# circuit.net
KiCad netlist of a schematic drawn in Altium Designer
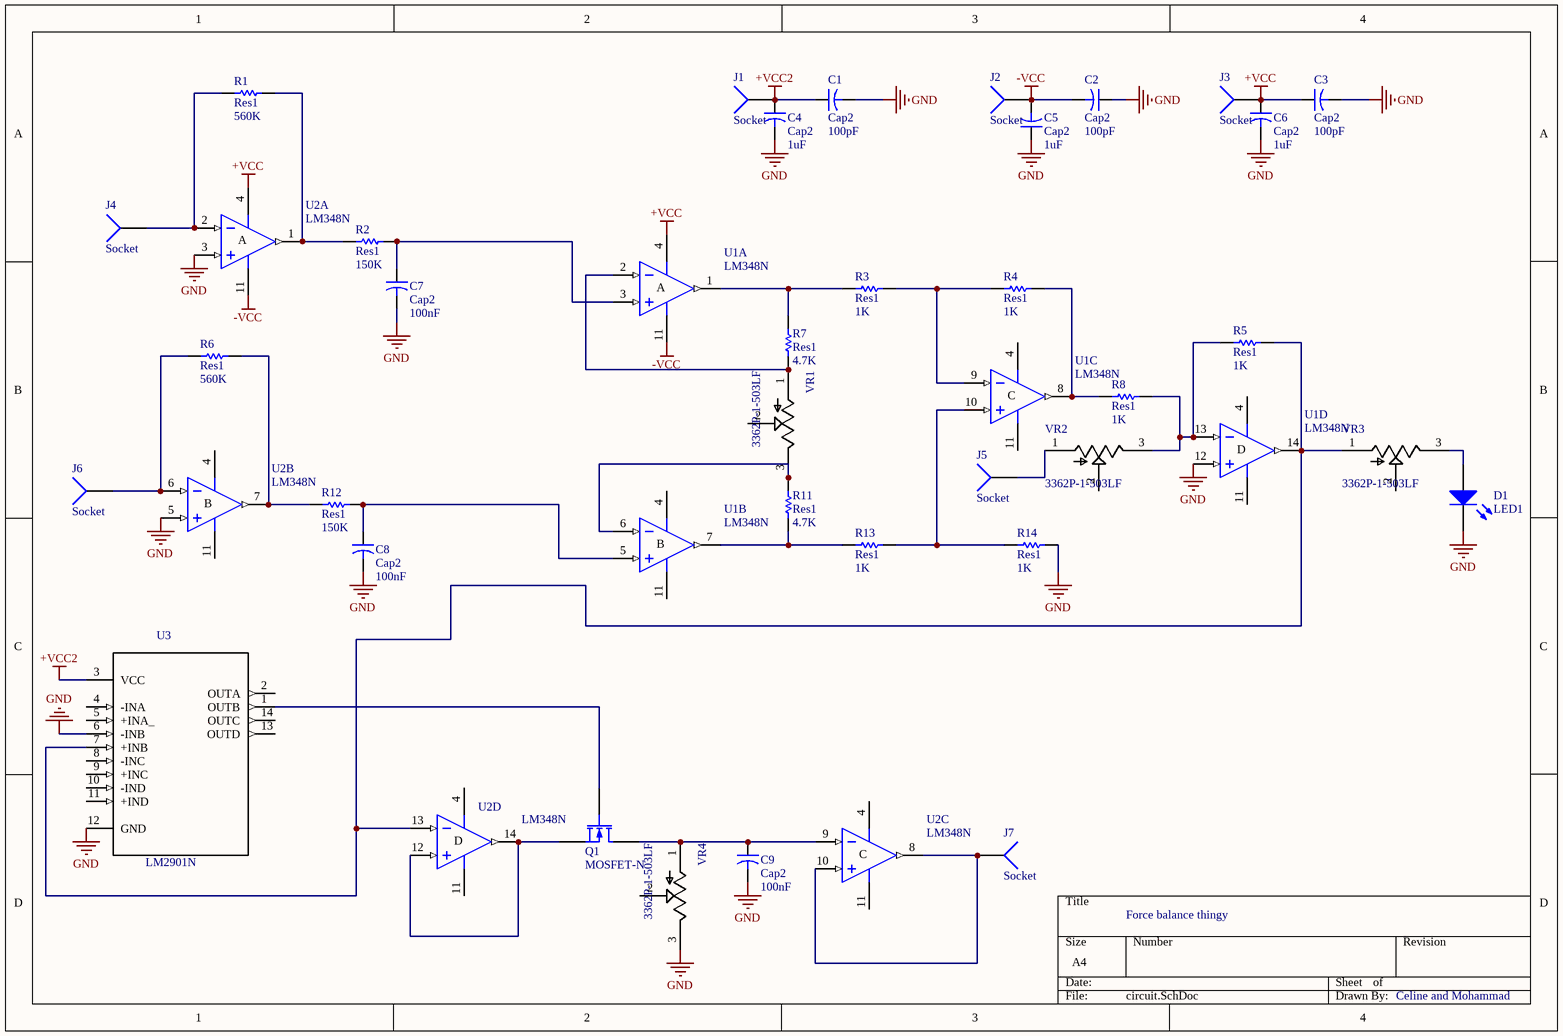
[diagram p0: circuit.SchDoc]

(export (version "E")
  (design (tool "Eeschema 10.0.6"))
  (components
    (comp (ref "C1")
      (value "Cap2")
      (footprint "CAPR5-4X5")
      (description "Capacitor")
      (fields (field (name "ALTIUM_VALUE") "100pF") (field (name "PUBLISHER") "Altium Limited"))
      (libsource (lib "Miscellaneous Devices") (part "Cap2"))
    )
    (comp (ref "C2")
      (value "Cap2")
      (footprint "CAPR5-4X5")
      (description "Capacitor")
      (fields (field (name "ALTIUM_VALUE") "100pF") (field (name "PUBLISHER") "Altium Limited"))
      (libsource (lib "Miscellaneous Devices") (part "Cap2"))
    )
    (comp (ref "C3")
      (value "Cap2")
      (footprint "CAPR5-4X5")
      (description "Capacitor")
      (fields (field (name "ALTIUM_VALUE") "100pF") (field (name "PUBLISHER") "Altium Limited"))
      (libsource (lib "Miscellaneous Devices") (part "Cap2"))
    )
    (comp (ref "C4")
      (value "Cap2")
      (footprint "CAPR5-4X5")
      (description "Capacitor")
      (fields (field (name "ALTIUM_VALUE") "1uF") (field (name "PUBLISHER") "Altium Limited"))
      (libsource (lib "Miscellaneous Devices") (part "Cap2"))
    )
    (comp (ref "C5")
      (value "Cap2")
      (footprint "CAPR5-4X5")
      (description "Capacitor")
      (fields (field (name "ALTIUM_VALUE") "1uF") (field (name "PUBLISHER") "Altium Limited"))
      (libsource (lib "Miscellaneous Devices") (part "Cap2"))
    )
    (comp (ref "C6")
      (value "Cap2")
      (footprint "CAPR5-4X5")
      (description "Capacitor")
      (fields (field (name "ALTIUM_VALUE") "1uF") (field (name "PUBLISHER") "Altium Limited"))
      (libsource (lib "Miscellaneous Devices") (part "Cap2"))
    )
    (comp (ref "C7")
      (value "Cap2")
      (footprint "CAPR5-4X5")
      (description "Capacitor")
      (fields (field (name "ALTIUM_VALUE") "100nF") (field (name "PUBLISHER") "Altium Limited"))
      (libsource (lib "Miscellaneous Devices") (part "Cap2"))
    )
    (comp (ref "C8")
      (value "Cap2")
      (footprint "CAPR5-4X5")
      (description "Capacitor")
      (fields (field (name "ALTIUM_VALUE") "100nF") (field (name "PUBLISHER") "Altium Limited"))
      (libsource (lib "Miscellaneous Devices") (part "Cap2"))
    )
    (comp (ref "C9")
      (value "Cap2")
      (footprint "CAPR5-4X5")
      (description "Capacitor")
      (fields (field (name "ALTIUM_VALUE") "100nF") (field (name "PUBLISHER") "Altium Limited"))
      (libsource (lib "Miscellaneous Devices") (part "Cap2"))
    )
    (comp (ref "D1")
      (value "LED1")
      (footprint "LED-1")
      (description "Typical RED GaAs LED")
      (fields (field (name "PUBLISHER") "Altium Limited"))
      (libsource (lib "Miscellaneous Devices") (part "LED1"))
    )
    (comp (ref "J1")
      (value "Socket")
      (footprint "PIN1")
      (fields (field (name "PUBLISHER") "Altium Limited"))
      (libsource (lib "Miscellaneous Connectors") (part "Socket"))
    )
    (comp (ref "J2")
      (value "Socket")
      (footprint "PIN1")
      (fields (field (name "PUBLISHER") "Altium Limited"))
      (libsource (lib "Miscellaneous Connectors") (part "Socket"))
    )
    (comp (ref "J3")
      (value "Socket")
      (footprint "PIN1")
      (fields (field (name "PUBLISHER") "Altium Limited"))
      (libsource (lib "Miscellaneous Connectors") (part "Socket"))
    )
    (comp (ref "J4")
      (value "Socket")
      (footprint "PIN1")
      (fields (field (name "PUBLISHER") "Altium Limited"))
      (libsource (lib "Miscellaneous Connectors") (part "Socket"))
    )
    (comp (ref "J5")
      (value "Socket")
      (footprint "PIN1")
      (fields (field (name "PUBLISHER") "Altium Limited"))
      (libsource (lib "Miscellaneous Connectors") (part "Socket"))
    )
    (comp (ref "J6")
      (value "Socket")
      (footprint "PIN1")
      (fields (field (name "PUBLISHER") "Altium Limited"))
      (libsource (lib "Miscellaneous Connectors") (part "Socket"))
    )
    (comp (ref "J7")
      (value "Socket")
      (footprint "PIN1")
      (fields (field (name "PUBLISHER") "Altium Limited"))
      (libsource (lib "Miscellaneous Connectors") (part "Socket"))
    )
    (comp (ref "Q1")
      (value "MOSFET-N")
      (footprint "E3")
      (description "N-Channel MOSFET")
      (fields (field (name "PUBLISHER") "Altium Limited"))
      (libsource (lib "Miscellaneous Devices") (part "MOSFET-N"))
    )
    (comp (ref "R1")
      (value "Res1")
      (footprint "AXIAL-0.3")
      (description "Resistor")
      (fields (field (name "ALTIUM_VALUE") "560K") (field (name "PUBLISHER") "Altium Limited"))
      (libsource (lib "Miscellaneous Devices") (part "Res1"))
    )
    (comp (ref "R2")
      (value "Res1")
      (footprint "AXIAL-0.3")
      (description "Resistor")
      (fields (field (name "ALTIUM_VALUE") "150K") (field (name "PUBLISHER") "Altium Limited"))
      (libsource (lib "Miscellaneous Devices") (part "Res1"))
    )
    (comp (ref "R3")
      (value "Res1")
      (footprint "AXIAL-0.3")
      (description "Resistor")
      (fields (field (name "ALTIUM_VALUE") "1K") (field (name "PUBLISHER") "Altium Limited"))
      (libsource (lib "Miscellaneous Devices") (part "Res1"))
    )
    (comp (ref "R4")
      (value "Res1")
      (footprint "AXIAL-0.3")
      (description "Resistor")
      (fields (field (name "ALTIUM_VALUE") "1K") (field (name "PUBLISHER") "Altium Limited"))
      (libsource (lib "Miscellaneous Devices") (part "Res1"))
    )
    (comp (ref "R5")
      (value "Res1")
      (footprint "AXIAL-0.3")
      (description "Resistor")
      (fields (field (name "ALTIUM_VALUE") "1K") (field (name "PUBLISHER") "Altium Limited"))
      (libsource (lib "Miscellaneous Devices") (part "Res1"))
    )
    (comp (ref "R6")
      (value "Res1")
      (footprint "AXIAL-0.3")
      (description "Resistor")
      (fields (field (name "ALTIUM_VALUE") "560K") (field (name "PUBLISHER") "Altium Limited"))
      (libsource (lib "Miscellaneous Devices") (part "Res1"))
    )
    (comp (ref "R7")
      (value "Res1")
      (footprint "AXIAL-0.3")
      (description "Resistor")
      (fields (field (name "ALTIUM_VALUE") "4.7K") (field (name "PUBLISHER") "Altium Limited"))
      (libsource (lib "Miscellaneous Devices") (part "Res1"))
    )
    (comp (ref "R8")
      (value "Res1")
      (footprint "AXIAL-0.3")
      (description "Resistor")
      (fields (field (name "ALTIUM_VALUE") "1K") (field (name "PUBLISHER") "Altium Limited"))
      (libsource (lib "Miscellaneous Devices") (part "Res1"))
    )
    (comp (ref "R11")
      (value "Res1")
      (footprint "AXIAL-0.3")
      (description "Resistor")
      (fields (field (name "ALTIUM_VALUE") "4.7K") (field (name "PUBLISHER") "Altium Limited"))
      (libsource (lib "Miscellaneous Devices") (part "Res1"))
    )
    (comp (ref "R12")
      (value "Res1")
      (footprint "AXIAL-0.3")
      (description "Resistor")
      (fields (field (name "ALTIUM_VALUE") "150K") (field (name "PUBLISHER") "Altium Limited"))
      (libsource (lib "Miscellaneous Devices") (part "Res1"))
    )
    (comp (ref "R13")
      (value "Res1")
      (footprint "AXIAL-0.3")
      (description "Resistor")
      (fields (field (name "ALTIUM_VALUE") "1K") (field (name "PUBLISHER") "Altium Limited"))
      (libsource (lib "Miscellaneous Devices") (part "Res1"))
    )
    (comp (ref "R14")
      (value "Res1")
      (footprint "AXIAL-0.3")
      (description "Resistor")
      (fields (field (name "ALTIUM_VALUE") "1K") (field (name "PUBLISHER") "Altium Limited"))
      (libsource (lib "Miscellaneous Devices") (part "Res1"))
    )
    (comp (ref "U1")
      (value "LM348N")
      (footprint "N014")
      (description "Quadruple Operational Amplifier")
      (fields (field (name "PUBLISHER") "Altium Limited"))
      (libsource (lib "TI Operational Amplifier") (part "LM348N"))
    )
    (comp (ref "U2")
      (value "LM348N")
      (footprint "N014")
      (description "Quadruple Operational Amplifier")
      (fields (field (name "PUBLISHER") "Altium Limited"))
      (libsource (lib "TI Operational Amplifier") (part "LM348N"))
    )
    (comp (ref "U3")
      (value "LM2901N")
      (footprint "*DIP254P762X508-14")
      (description "Low Power Low Offset Voltage Quad Comparator 14-PDIP -40 to 85")
      (fields (field (name "MF") "Texas Instruments") (field (name "MP") "LM2901N/NOPB"))
      (libsource (lib "LM2901N") (part "LM2901N"))
    )
    (comp (ref "VR1")
      (value "3362P-1-503LF")
      (footprint "*TRIM_3362P-1-503LF")
      (fields (field (name "MF") "Bourns") (field (name "DIGI-KEY_PART_NUMBER") "3362P-503LF-ND"))
      (libsource (lib "3362P-1-503LF") (part "3362P-1-503LF"))
    )
    (comp (ref "VR2")
      (value "3362P-1-503LF")
      (footprint "*TRIM_3362P-1-503LF")
      (fields (field (name "MF") "Bourns") (field (name "DIGI-KEY_PART_NUMBER") "3362P-503LF-ND"))
      (libsource (lib "3362P-1-503LF") (part "3362P-1-503LF"))
    )
    (comp (ref "VR3")
      (value "3362P-1-503LF")
      (footprint "*TRIM_3362P-1-503LF")
      (fields (field (name "MF") "Bourns") (field (name "DIGI-KEY_PART_NUMBER") "3362P-503LF-ND"))
      (libsource (lib "3362P-1-503LF") (part "3362P-1-503LF"))
    )
    (comp (ref "VR4")
      (value "3362P-1-503LF")
      (footprint "*TRIM_3362P-1-503LF")
      (fields (field (name "MF") "Bourns") (field (name "DIGI-KEY_PART_NUMBER") "3362P-503LF-ND"))
      (libsource (lib "3362P-1-503LF") (part "3362P-1-503LF"))
    )
  )
  (nets
    (net (code "1") (name "+VCC") (class "Default")
      (node (ref "C3") (pin "1") (pinfunction "1_1") (pintype "passive"))
      (node (ref "C6") (pin "1") (pinfunction "1_1") (pintype "passive"))
      (node (ref "J3") (pin "1") (pinfunction "1_1") (pintype "passive"))
      (node (ref "U1") (pin "4") (pinfunction "V+_4") (pintype "power_in"))
      (node (ref "U2") (pin "4") (pinfunction "V+_4") (pintype "power_in"))
    )
    (net (code "2") (name "+VCC2") (class "Default")
      (node (ref "C1") (pin "1") (pinfunction "1_1") (pintype "passive"))
      (node (ref "C4") (pin "1") (pinfunction "1_1") (pintype "passive"))
      (node (ref "J1") (pin "1") (pinfunction "1_1") (pintype "passive"))
      (node (ref "U3") (pin "3") (pinfunction "VCC_3") (pintype "passive"))
    )
    (net (code "3") (name "-VCC") (class "Default")
      (node (ref "C2") (pin "2") (pinfunction "2_2") (pintype "passive"))
      (node (ref "C5") (pin "2") (pinfunction "2_2") (pintype "passive"))
      (node (ref "J2") (pin "1") (pinfunction "1_1") (pintype "passive"))
      (node (ref "U1") (pin "11") (pinfunction "V-_11") (pintype "power_in"))
      (node (ref "U2") (pin "11") (pinfunction "V-_11") (pintype "power_in"))
    )
    (net (code "4") (name "GND") (class "Default")
      (node (ref "C1") (pin "2") (pinfunction "2_2") (pintype "passive"))
      (node (ref "C2") (pin "1") (pinfunction "1_1") (pintype "passive"))
      (node (ref "C3") (pin "2") (pinfunction "2_2") (pintype "passive"))
      (node (ref "C4") (pin "2") (pinfunction "2_2") (pintype "passive"))
      (node (ref "C5") (pin "1") (pinfunction "1_1") (pintype "passive"))
      (node (ref "C6") (pin "2") (pinfunction "2_2") (pintype "passive"))
      (node (ref "C7") (pin "2") (pinfunction "2_2") (pintype "passive"))
      (node (ref "C8") (pin "2") (pinfunction "2_2") (pintype "passive"))
      (node (ref "C9") (pin "2") (pinfunction "2_2") (pintype "passive"))
      (node (ref "D1") (pin "2") (pinfunction "K_2") (pintype "passive"))
      (node (ref "R14") (pin "2") (pinfunction "2_2") (pintype "passive"))
      (node (ref "U1") (pin "12") (pinfunction "IN+_12") (pintype "input"))
      (node (ref "U2") (pin "3") (pinfunction "IN+_3") (pintype "input"))
      (node (ref "U2") (pin "5") (pinfunction "IN+_5") (pintype "input"))
      (node (ref "U3") (pin "12") (pinfunction "GND_12") (pintype "passive"))
      (node (ref "U3") (pin "6") (pinfunction "-INB_6") (pintype "input"))
      (node (ref "VR4") (pin "3") (pinfunction "CW_3") (pintype "passive"))
    )
    (net (code "5") (name "Net-(D1-A)") (class "Default")
      (node (ref "D1") (pin "1") (pinfunction "A_1") (pintype "passive"))
      (node (ref "VR3") (pin "3") (pinfunction "CW_3") (pintype "passive"))
    )
    (net (code "6") (name "Net-(Q1-D)") (class "Default")
      (node (ref "C9") (pin "1") (pinfunction "1_1") (pintype "passive"))
      (node (ref "Q1") (pin "1") (pinfunction "D_1") (pintype "passive"))
      (node (ref "U2") (pin "9") (pinfunction "IN-_9") (pintype "input"))
      (node (ref "VR4") (pin "1") (pinfunction "CCW_1") (pintype "passive"))
    )
    (net (code "7") (name "Net-(Q1-G)") (class "Default")
      (node (ref "Q1") (pin "2") (pinfunction "G_2") (pintype "passive"))
      (node (ref "U3") (pin "1") (pinfunction "OUTB_1") (pintype "output"))
    )
    (net (code "8") (name "Net-(Q1-S)") (class "Default")
      (node (ref "Q1") (pin "3") (pinfunction "S_3") (pintype "passive"))
      (node (ref "U2") (pin "12") (pinfunction "IN+_12") (pintype "input"))
      (node (ref "U2") (pin "14") (pinfunction "OUT_14") (pintype "output"))
    )
    (net (code "9") (name "Net-(U1A-IN+)") (class "Default")
      (node (ref "C7") (pin "1") (pinfunction "1_1") (pintype "passive"))
      (node (ref "R2") (pin "2") (pinfunction "2_2") (pintype "passive"))
      (node (ref "U1") (pin "3") (pinfunction "IN+_3") (pintype "input"))
    )
    (net (code "10") (name "Net-(U1A-IN-)") (class "Default")
      (node (ref "R7") (pin "1") (pinfunction "1_1") (pintype "passive"))
      (node (ref "U1") (pin "2") (pinfunction "IN-_2") (pintype "input"))
      (node (ref "VR1") (pin "1") (pinfunction "CCW_1") (pintype "passive"))
    )
    (net (code "11") (name "Net-(U1A-OUT)") (class "Default")
      (node (ref "R3") (pin "1") (pinfunction "1_1") (pintype "passive"))
      (node (ref "R7") (pin "2") (pinfunction "2_2") (pintype "passive"))
      (node (ref "U1") (pin "1") (pinfunction "OUT_1") (pintype "output"))
    )
    (net (code "12") (name "Net-(U1B-IN+)") (class "Default")
      (node (ref "C8") (pin "1") (pinfunction "1_1") (pintype "passive"))
      (node (ref "R12") (pin "2") (pinfunction "2_2") (pintype "passive"))
      (node (ref "U1") (pin "5") (pinfunction "IN+_5") (pintype "input"))
    )
    (net (code "13") (name "Net-(U1B-IN-)") (class "Default")
      (node (ref "R11") (pin "2") (pinfunction "2_2") (pintype "passive"))
      (node (ref "U1") (pin "6") (pinfunction "IN-_6") (pintype "input"))
      (node (ref "VR1") (pin "3") (pinfunction "CW_3") (pintype "passive"))
    )
    (net (code "14") (name "Net-(U1B-OUT)") (class "Default")
      (node (ref "R11") (pin "1") (pinfunction "1_1") (pintype "passive"))
      (node (ref "R13") (pin "1") (pinfunction "1_1") (pintype "passive"))
      (node (ref "U1") (pin "7") (pinfunction "OUT_7") (pintype "output"))
    )
    (net (code "15") (name "Net-(U1C-IN+)") (class "Default")
      (node (ref "R13") (pin "2") (pinfunction "2_2") (pintype "passive"))
      (node (ref "R14") (pin "1") (pinfunction "1_1") (pintype "passive"))
      (node (ref "U1") (pin "10") (pinfunction "IN+_10") (pintype "input"))
    )
    (net (code "16") (name "Net-(U1C-IN-)") (class "Default")
      (node (ref "R3") (pin "2") (pinfunction "2_2") (pintype "passive"))
      (node (ref "R4") (pin "1") (pinfunction "1_1") (pintype "passive"))
      (node (ref "U1") (pin "9") (pinfunction "IN-_9") (pintype "input"))
    )
    (net (code "17") (name "Net-(U1C-OUT)") (class "Default")
      (node (ref "R4") (pin "2") (pinfunction "2_2") (pintype "passive"))
      (node (ref "R8") (pin "1") (pinfunction "1_1") (pintype "passive"))
      (node (ref "U1") (pin "8") (pinfunction "OUT_8") (pintype "output"))
    )
    (net (code "18") (name "Net-(U1D-IN-)") (class "Default")
      (node (ref "R5") (pin "1") (pinfunction "1_1") (pintype "passive"))
      (node (ref "R8") (pin "2") (pinfunction "2_2") (pintype "passive"))
      (node (ref "U1") (pin "13") (pinfunction "IN-_13") (pintype "input"))
      (node (ref "VR2") (pin "3") (pinfunction "CW_3") (pintype "passive"))
    )
    (net (code "19") (name "Net-(U1D-OUT)") (class "Default")
      (node (ref "R5") (pin "2") (pinfunction "2_2") (pintype "passive"))
      (node (ref "U1") (pin "14") (pinfunction "OUT_14") (pintype "output"))
      (node (ref "U2") (pin "13") (pinfunction "IN-_13") (pintype "input"))
      (node (ref "U3") (pin "7") (pinfunction "+INB_7") (pintype "input"))
      (node (ref "VR3") (pin "1") (pinfunction "CCW_1") (pintype "passive"))
    )
    (net (code "20") (name "Net-(U2A-IN-)") (class "Default")
      (node (ref "J4") (pin "1") (pinfunction "1_1") (pintype "passive"))
      (node (ref "R1") (pin "1") (pinfunction "1_1") (pintype "passive"))
      (node (ref "U2") (pin "2") (pinfunction "IN-_2") (pintype "input"))
    )
    (net (code "21") (name "Net-(U2A-OUT)") (class "Default")
      (node (ref "R1") (pin "2") (pinfunction "2_2") (pintype "passive"))
      (node (ref "R2") (pin "1") (pinfunction "1_1") (pintype "passive"))
      (node (ref "U2") (pin "1") (pinfunction "OUT_1") (pintype "output"))
    )
    (net (code "22") (name "Net-(U2B-IN-)") (class "Default")
      (node (ref "J6") (pin "1") (pinfunction "1_1") (pintype "passive"))
      (node (ref "R6") (pin "1") (pinfunction "1_1") (pintype "passive"))
      (node (ref "U2") (pin "6") (pinfunction "IN-_6") (pintype "input"))
    )
    (net (code "23") (name "Net-(U2B-OUT)") (class "Default")
      (node (ref "R12") (pin "1") (pinfunction "1_1") (pintype "passive"))
      (node (ref "R6") (pin "2") (pinfunction "2_2") (pintype "passive"))
      (node (ref "U2") (pin "7") (pinfunction "OUT_7") (pintype "output"))
    )
    (net (code "24") (name "Net-(U2C-IN+)") (class "Default")
      (node (ref "J7") (pin "1") (pinfunction "1_1") (pintype "passive"))
      (node (ref "U2") (pin "10") (pinfunction "IN+_10") (pintype "input"))
      (node (ref "U2") (pin "8") (pinfunction "OUT_8") (pintype "output"))
    )
    (net (code "25") (name "Net-(VR2-CCW)") (class "Default")
      (node (ref "J5") (pin "1") (pinfunction "1_1") (pintype "passive"))
      (node (ref "VR2") (pin "1") (pinfunction "CCW_1") (pintype "passive"))
    )
    (net (code "26") (name "unconnected-(U1B-V+-Pad4)") (class "Default")
      (node (ref "U1") (pin "4") (pinfunction "V+_4") (pintype "power_in"))
    )
    (net (code "27") (name "unconnected-(U1B-V--Pad11)") (class "Default")
      (node (ref "U1") (pin "11") (pinfunction "V-_11") (pintype "power_in"))
    )
    (net (code "28") (name "unconnected-(U1C-V+-Pad4)") (class "Default")
      (node (ref "U1") (pin "4") (pinfunction "V+_4") (pintype "power_in"))
    )
    (net (code "29") (name "unconnected-(U1C-V--Pad11)") (class "Default")
      (node (ref "U1") (pin "11") (pinfunction "V-_11") (pintype "power_in"))
    )
    (net (code "30") (name "unconnected-(U1D-V+-Pad4)") (class "Default")
      (node (ref "U1") (pin "4") (pinfunction "V+_4") (pintype "power_in"))
    )
    (net (code "31") (name "unconnected-(U1D-V--Pad11)") (class "Default")
      (node (ref "U1") (pin "11") (pinfunction "V-_11") (pintype "power_in"))
    )
    (net (code "32") (name "unconnected-(U2B-V+-Pad4)") (class "Default")
      (node (ref "U2") (pin "4") (pinfunction "V+_4") (pintype "power_in"))
    )
    (net (code "33") (name "unconnected-(U2B-V--Pad11)") (class "Default")
      (node (ref "U2") (pin "11") (pinfunction "V-_11") (pintype "power_in"))
    )
    (net (code "34") (name "unconnected-(U2C-V+-Pad4)") (class "Default")
      (node (ref "U2") (pin "4") (pinfunction "V+_4") (pintype "power_in"))
    )
    (net (code "35") (name "unconnected-(U2C-V--Pad11)") (class "Default")
      (node (ref "U2") (pin "11") (pinfunction "V-_11") (pintype "power_in"))
    )
    (net (code "36") (name "unconnected-(U2D-V+-Pad4)") (class "Default")
      (node (ref "U2") (pin "4") (pinfunction "V+_4") (pintype "power_in"))
    )
    (net (code "37") (name "unconnected-(U2D-V--Pad11)") (class "Default")
      (node (ref "U2") (pin "11") (pinfunction "V-_11") (pintype "power_in"))
    )
    (net (code "38") (name "unconnected-(U3-+INA_-Pad5)") (class "Default")
      (node (ref "U3") (pin "5") (pinfunction "+INA__5") (pintype "input"))
    )
    (net (code "39") (name "unconnected-(U3-+INC-Pad9)") (class "Default")
      (node (ref "U3") (pin "9") (pinfunction "+INC_9") (pintype "input"))
    )
    (net (code "40") (name "unconnected-(U3-+IND-Pad11)") (class "Default")
      (node (ref "U3") (pin "11") (pinfunction "+IND_11") (pintype "input"))
    )
    (net (code "41") (name "unconnected-(U3--INA-Pad4)") (class "Default")
      (node (ref "U3") (pin "4") (pinfunction "-INA_4") (pintype "input"))
    )
    (net (code "42") (name "unconnected-(U3--INC-Pad8)") (class "Default")
      (node (ref "U3") (pin "8") (pinfunction "-INC_8") (pintype "input"))
    )
    (net (code "43") (name "unconnected-(U3--IND-Pad10)") (class "Default")
      (node (ref "U3") (pin "10") (pinfunction "-IND_10") (pintype "input"))
    )
    (net (code "44") (name "unconnected-(U3-OUTA-Pad2)") (class "Default")
      (node (ref "U3") (pin "2") (pinfunction "OUTA_2") (pintype "output"))
    )
    (net (code "45") (name "unconnected-(U3-OUTC-Pad14)") (class "Default")
      (node (ref "U3") (pin "14") (pinfunction "OUTC_14") (pintype "output"))
    )
    (net (code "46") (name "unconnected-(U3-OUTD-Pad13)") (class "Default")
      (node (ref "U3") (pin "13") (pinfunction "OUTD_13") (pintype "output"))
    )
    (net (code "47") (name "unconnected-(VR1-WIPER-Pad2)") (class "Default")
      (node (ref "VR1") (pin "2") (pinfunction "WIPER_2") (pintype "passive"))
    )
    (net (code "48") (name "unconnected-(VR2-WIPER-Pad2)") (class "Default")
      (node (ref "VR2") (pin "2") (pinfunction "WIPER_2") (pintype "passive"))
    )
    (net (code "49") (name "unconnected-(VR3-WIPER-Pad2)") (class "Default")
      (node (ref "VR3") (pin "2") (pinfunction "WIPER_2") (pintype "passive"))
    )
    (net (code "50") (name "unconnected-(VR4-WIPER-Pad2)") (class "Default")
      (node (ref "VR4") (pin "2") (pinfunction "WIPER_2") (pintype "passive"))
    )
  )
)
